# mosfets.net
KiCad netlist of a schematic drawn in Altium Designer
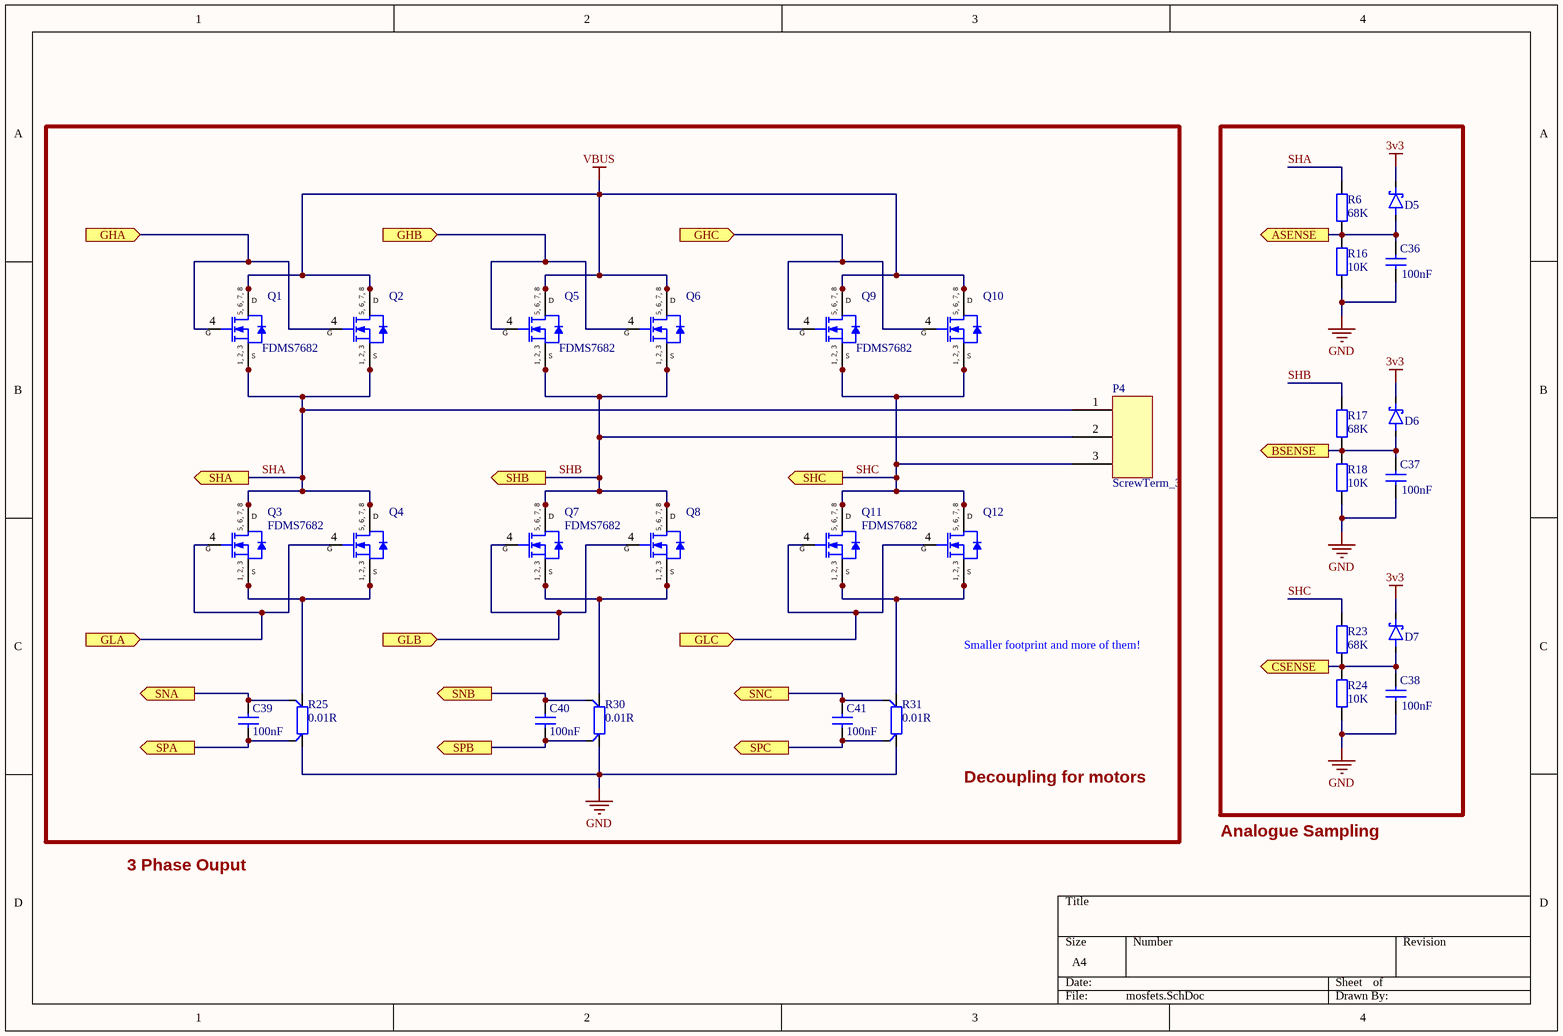
[diagram p0: mosfets.SchDoc]

(export (version "E")
  (design (tool "Eeschema 10.0.6"))
  (components
    (comp (ref "C36")
      (value "100nF")
      (footprint "CAP0402(1005)_N")
      (description "Capacitor")
      (fields (field (name "PART") "cap_generic"))
      (libsource (lib "hitiqlib") (part "cap"))
    )
    (comp (ref "C37")
      (value "100nF")
      (footprint "CAP0402(1005)_N")
      (description "Capacitor")
      (fields (field (name "PART") "cap_generic"))
      (libsource (lib "hitiqlib") (part "cap"))
    )
    (comp (ref "C38")
      (value "100nF")
      (footprint "CAP0402(1005)_N")
      (description "Capacitor")
      (fields (field (name "PART") "cap_generic"))
      (libsource (lib "hitiqlib") (part "cap"))
    )
    (comp (ref "C39")
      (value "100nF")
      (footprint "CAP0402(1005)_N")
      (description "Capacitor")
      (fields (field (name "PART") "cap_generic"))
      (libsource (lib "hitiqlib") (part "cap"))
    )
    (comp (ref "C40")
      (value "100nF")
      (footprint "CAP0402(1005)_N")
      (description "Capacitor")
      (fields (field (name "PART") "cap_generic"))
      (libsource (lib "hitiqlib") (part "cap"))
    )
    (comp (ref "C41")
      (value "100nF")
      (footprint "CAP0402(1005)_N")
      (description "Capacitor")
      (fields (field (name "PART") "cap_generic"))
      (libsource (lib "hitiqlib") (part "cap"))
    )
    (comp (ref "D5")
      (value "Diode_schottky")
      (footprint "SOD523")
      (libsource (lib "myPassives") (part "Diode_schottky"))
    )
    (comp (ref "D6")
      (value "Diode_schottky")
      (footprint "SOD523")
      (libsource (lib "myPassives") (part "Diode_schottky"))
    )
    (comp (ref "D7")
      (value "Diode_schottky")
      (footprint "SOD523")
      (libsource (lib "myPassives") (part "Diode_schottky"))
    )
    (comp (ref "P4")
      (value "ScrewTerm_3")
      (footprint "ScrewTerm_3")
      (libsource (lib "Seeed") (part "ScrewTerm_3"))
    )
    (comp (ref "Q1") (value "FDMS7682") (footprint "PQFN8_5x6") (libsource (lib "myLibs") (part "FDMS7682")))
    (comp (ref "Q2") (value "FDMS7682") (footprint "PQFN8_5x6") (libsource (lib "myLibs") (part "FDMS7682")))
    (comp (ref "Q3") (value "FDMS7682") (footprint "PQFN8_5x6") (libsource (lib "myLibs") (part "FDMS7682")))
    (comp (ref "Q4") (value "FDMS7682") (footprint "PQFN8_5x6") (libsource (lib "myLibs") (part "FDMS7682")))
    (comp (ref "Q5") (value "FDMS7682") (footprint "PQFN8_5x6") (libsource (lib "myLibs") (part "FDMS7682")))
    (comp (ref "Q6") (value "FDMS7682") (footprint "PQFN8_5x6") (libsource (lib "myLibs") (part "FDMS7682")))
    (comp (ref "Q7") (value "FDMS7682") (footprint "PQFN8_5x6") (libsource (lib "myLibs") (part "FDMS7682")))
    (comp (ref "Q8") (value "FDMS7682") (footprint "PQFN8_5x6") (libsource (lib "myLibs") (part "FDMS7682")))
    (comp (ref "Q9") (value "FDMS7682") (footprint "PQFN8_5x6") (libsource (lib "myLibs") (part "FDMS7682")))
    (comp (ref "Q10") (value "FDMS7682") (footprint "PQFN8_5x6") (libsource (lib "myLibs") (part "FDMS7682")))
    (comp (ref "Q11") (value "FDMS7682") (footprint "PQFN8_5x6") (libsource (lib "myLibs") (part "FDMS7682")))
    (comp (ref "Q12") (value "FDMS7682") (footprint "PQFN8_5x6") (libsource (lib "myLibs") (part "FDMS7682")))
    (comp (ref "R6")
      (value "68K")
      (footprint "RESC0402(1005)_N")
      (description "Resistor")
      (fields (field (name "PART") "res_generic"))
      (libsource (lib "hitiqlib") (part "Resistor"))
    )
    (comp (ref "R16")
      (value "10K")
      (footprint "RESC0402(1005)_N")
      (description "Resistor")
      (fields (field (name "PART") "res_generic"))
      (libsource (lib "hitiqlib") (part "Resistor"))
    )
    (comp (ref "R17")
      (value "68K")
      (footprint "RESC0402(1005)_N")
      (description "Resistor")
      (fields (field (name "PART") "res_generic"))
      (libsource (lib "hitiqlib") (part "Resistor"))
    )
    (comp (ref "R18")
      (value "10K")
      (footprint "RESC0402(1005)_N")
      (description "Resistor")
      (fields (field (name "PART") "res_generic"))
      (libsource (lib "hitiqlib") (part "Resistor"))
    )
    (comp (ref "R23")
      (value "68K")
      (footprint "RESC0402(1005)_N")
      (description "Resistor")
      (fields (field (name "PART") "res_generic"))
      (libsource (lib "hitiqlib") (part "Resistor"))
    )
    (comp (ref "R24")
      (value "10K")
      (footprint "RESC0402(1005)_N")
      (description "Resistor")
      (fields (field (name "PART") "res_generic"))
      (libsource (lib "hitiqlib") (part "Resistor"))
    )
    (comp (ref "R25")
      (value "0.01R")
      (footprint "RESC1206_kelvin")
      (description "Kelvin connection resistor")
      (fields (field (name "PART") "Generic_res_kelvin"))
      (libsource (lib "hitiqlib") (part "Resistor_kelvin"))
    )
    (comp (ref "R30")
      (value "0.01R")
      (footprint "RESC1206_kelvin")
      (description "Kelvin connection resistor")
      (fields (field (name "PART") "Generic_res_kelvin"))
      (libsource (lib "hitiqlib") (part "Resistor_kelvin"))
    )
    (comp (ref "R31")
      (value "0.01R")
      (footprint "RESC1206_kelvin")
      (description "Kelvin connection resistor")
      (fields (field (name "PART") "Generic_res_kelvin"))
      (libsource (lib "hitiqlib") (part "Resistor_kelvin"))
    )
  )
  (nets
    (net (code "1") (name "/ASENSE") (class "Default")
      (node (ref "C36") (pin "2") (pintype "passive"))
      (node (ref "D5") (pin "2") (pintype "passive"))
      (node (ref "R16") (pin "2") (pintype "passive"))
      (node (ref "R6") (pin "1") (pintype "passive"))
    )
    (net (code "2") (name "/BSENSE") (class "Default")
      (node (ref "C37") (pin "2") (pintype "passive"))
      (node (ref "D6") (pin "2") (pintype "passive"))
      (node (ref "R17") (pin "1") (pintype "passive"))
      (node (ref "R18") (pin "2") (pintype "passive"))
    )
    (net (code "3") (name "/CSENSE") (class "Default")
      (node (ref "C38") (pin "2") (pintype "passive"))
      (node (ref "D7") (pin "2") (pintype "passive"))
      (node (ref "R23") (pin "1") (pintype "passive"))
      (node (ref "R24") (pin "2") (pintype "passive"))
    )
    (net (code "4") (name "/GHA") (class "Default")
      (node (ref "Q1") (pin "4") (pinfunction "G_4") (pintype "passive"))
      (node (ref "Q2") (pin "4") (pinfunction "G_4") (pintype "passive"))
    )
    (net (code "5") (name "/GHB") (class "Default")
      (node (ref "Q5") (pin "4") (pinfunction "G_4") (pintype "passive"))
      (node (ref "Q6") (pin "4") (pinfunction "G_4") (pintype "passive"))
    )
    (net (code "6") (name "/GHC") (class "Default")
      (node (ref "Q10") (pin "4") (pinfunction "G_4") (pintype "passive"))
      (node (ref "Q9") (pin "4") (pinfunction "G_4") (pintype "passive"))
    )
    (net (code "7") (name "/GLA") (class "Default")
      (node (ref "Q3") (pin "4") (pinfunction "G_4") (pintype "passive"))
      (node (ref "Q4") (pin "4") (pinfunction "G_4") (pintype "passive"))
    )
    (net (code "8") (name "/GLB") (class "Default")
      (node (ref "Q7") (pin "4") (pinfunction "G_4") (pintype "passive"))
      (node (ref "Q8") (pin "4") (pinfunction "G_4") (pintype "passive"))
    )
    (net (code "9") (name "/GLC") (class "Default")
      (node (ref "Q11") (pin "4") (pinfunction "G_4") (pintype "passive"))
      (node (ref "Q12") (pin "4") (pinfunction "G_4") (pintype "passive"))
    )
    (net (code "10") (name "/SHA") (class "Default")
      (node (ref "P4") (pin "1") (pintype "passive"))
      (node (ref "Q1") (pin "1") (pinfunction "S_1") (pintype "passive"))
      (node (ref "Q1") (pin "2") (pinfunction "S_2") (pintype "power_in"))
      (node (ref "Q1") (pin "3") (pinfunction "S_3") (pintype "power_in"))
      (node (ref "Q2") (pin "1") (pinfunction "S_1") (pintype "passive"))
      (node (ref "Q2") (pin "2") (pinfunction "S_2") (pintype "power_in"))
      (node (ref "Q2") (pin "3") (pinfunction "S_3") (pintype "power_in"))
      (node (ref "Q3") (pin "0") (pinfunction "D_0") (pintype "passive"))
      (node (ref "Q3") (pin "5") (pinfunction "D_5") (pintype "passive"))
      (node (ref "Q3") (pin "6") (pinfunction "D_6") (pintype "passive"))
      (node (ref "Q3") (pin "7") (pinfunction "D_7") (pintype "passive"))
      (node (ref "Q3") (pin "8") (pinfunction "D_8") (pintype "passive"))
      (node (ref "Q4") (pin "0") (pinfunction "D_0") (pintype "passive"))
      (node (ref "Q4") (pin "5") (pinfunction "D_5") (pintype "passive"))
      (node (ref "Q4") (pin "6") (pinfunction "D_6") (pintype "passive"))
      (node (ref "Q4") (pin "7") (pinfunction "D_7") (pintype "passive"))
      (node (ref "Q4") (pin "8") (pinfunction "D_8") (pintype "passive"))
      (node (ref "R6") (pin "2") (pintype "passive"))
    )
    (net (code "11") (name "/SHB") (class "Default")
      (node (ref "P4") (pin "2") (pintype "passive"))
      (node (ref "Q5") (pin "1") (pinfunction "S_1") (pintype "passive"))
      (node (ref "Q5") (pin "2") (pinfunction "S_2") (pintype "power_in"))
      (node (ref "Q5") (pin "3") (pinfunction "S_3") (pintype "power_in"))
      (node (ref "Q6") (pin "1") (pinfunction "S_1") (pintype "passive"))
      (node (ref "Q6") (pin "2") (pinfunction "S_2") (pintype "power_in"))
      (node (ref "Q6") (pin "3") (pinfunction "S_3") (pintype "power_in"))
      (node (ref "Q7") (pin "0") (pinfunction "D_0") (pintype "passive"))
      (node (ref "Q7") (pin "5") (pinfunction "D_5") (pintype "passive"))
      (node (ref "Q7") (pin "6") (pinfunction "D_6") (pintype "passive"))
      (node (ref "Q7") (pin "7") (pinfunction "D_7") (pintype "passive"))
      (node (ref "Q7") (pin "8") (pinfunction "D_8") (pintype "passive"))
      (node (ref "Q8") (pin "0") (pinfunction "D_0") (pintype "passive"))
      (node (ref "Q8") (pin "5") (pinfunction "D_5") (pintype "passive"))
      (node (ref "Q8") (pin "6") (pinfunction "D_6") (pintype "passive"))
      (node (ref "Q8") (pin "7") (pinfunction "D_7") (pintype "passive"))
      (node (ref "Q8") (pin "8") (pinfunction "D_8") (pintype "passive"))
      (node (ref "R17") (pin "2") (pintype "passive"))
    )
    (net (code "12") (name "/SHC") (class "Default")
      (node (ref "P4") (pin "3") (pintype "passive"))
      (node (ref "Q10") (pin "1") (pinfunction "S_1") (pintype "passive"))
      (node (ref "Q10") (pin "2") (pinfunction "S_2") (pintype "power_in"))
      (node (ref "Q10") (pin "3") (pinfunction "S_3") (pintype "power_in"))
      (node (ref "Q11") (pin "0") (pinfunction "D_0") (pintype "passive"))
      (node (ref "Q11") (pin "5") (pinfunction "D_5") (pintype "passive"))
      (node (ref "Q11") (pin "6") (pinfunction "D_6") (pintype "passive"))
      (node (ref "Q11") (pin "7") (pinfunction "D_7") (pintype "passive"))
      (node (ref "Q11") (pin "8") (pinfunction "D_8") (pintype "passive"))
      (node (ref "Q12") (pin "0") (pinfunction "D_0") (pintype "passive"))
      (node (ref "Q12") (pin "5") (pinfunction "D_5") (pintype "passive"))
      (node (ref "Q12") (pin "6") (pinfunction "D_6") (pintype "passive"))
      (node (ref "Q12") (pin "7") (pinfunction "D_7") (pintype "passive"))
      (node (ref "Q12") (pin "8") (pinfunction "D_8") (pintype "passive"))
      (node (ref "Q9") (pin "1") (pinfunction "S_1") (pintype "passive"))
      (node (ref "Q9") (pin "2") (pinfunction "S_2") (pintype "power_in"))
      (node (ref "Q9") (pin "3") (pinfunction "S_3") (pintype "power_in"))
      (node (ref "R23") (pin "2") (pintype "passive"))
    )
    (net (code "13") (name "/SNA") (class "Default")
      (node (ref "C39") (pin "2") (pintype "passive"))
      (node (ref "R25") (pin "3") (pinfunction "3_3") (pintype "passive"))
    )
    (net (code "14") (name "/SNB") (class "Default")
      (node (ref "C40") (pin "2") (pintype "passive"))
      (node (ref "R30") (pin "3") (pinfunction "3_3") (pintype "passive"))
    )
    (net (code "15") (name "/SNC") (class "Default")
      (node (ref "C41") (pin "2") (pintype "passive"))
      (node (ref "R31") (pin "3") (pinfunction "3_3") (pintype "passive"))
    )
    (net (code "16") (name "/SPA") (class "Default")
      (node (ref "C39") (pin "1") (pintype "passive"))
      (node (ref "R25") (pin "4") (pinfunction "4_4") (pintype "passive"))
    )
    (net (code "17") (name "/SPB") (class "Default")
      (node (ref "C40") (pin "1") (pintype "passive"))
      (node (ref "R30") (pin "4") (pinfunction "4_4") (pintype "passive"))
    )
    (net (code "18") (name "/SPC") (class "Default")
      (node (ref "C41") (pin "1") (pintype "passive"))
      (node (ref "R31") (pin "4") (pinfunction "4_4") (pintype "passive"))
    )
    (net (code "19") (name "3v3") (class "Default")
      (node (ref "D5") (pin "1") (pintype "passive"))
      (node (ref "D6") (pin "1") (pintype "passive"))
      (node (ref "D7") (pin "1") (pintype "passive"))
    )
    (net (code "20") (name "GND") (class "Default")
      (node (ref "C36") (pin "1") (pintype "passive"))
      (node (ref "C37") (pin "1") (pintype "passive"))
      (node (ref "C38") (pin "1") (pintype "passive"))
      (node (ref "R16") (pin "1") (pintype "passive"))
      (node (ref "R18") (pin "1") (pintype "passive"))
      (node (ref "R24") (pin "1") (pintype "passive"))
      (node (ref "R25") (pin "2") (pintype "passive"))
      (node (ref "R30") (pin "2") (pintype "passive"))
      (node (ref "R31") (pin "2") (pintype "passive"))
    )
    (net (code "21") (name "Net-(Q3-S-Pad1)") (class "Default")
      (node (ref "Q3") (pin "1") (pinfunction "S_1") (pintype "passive"))
      (node (ref "Q3") (pin "2") (pinfunction "S_2") (pintype "power_in"))
      (node (ref "Q3") (pin "3") (pinfunction "S_3") (pintype "power_in"))
      (node (ref "Q4") (pin "1") (pinfunction "S_1") (pintype "passive"))
      (node (ref "Q4") (pin "2") (pinfunction "S_2") (pintype "power_in"))
      (node (ref "Q4") (pin "3") (pinfunction "S_3") (pintype "power_in"))
      (node (ref "R25") (pin "1") (pintype "passive"))
    )
    (net (code "22") (name "Net-(Q7-S-Pad1)") (class "Default")
      (node (ref "Q7") (pin "1") (pinfunction "S_1") (pintype "passive"))
      (node (ref "Q7") (pin "2") (pinfunction "S_2") (pintype "power_in"))
      (node (ref "Q7") (pin "3") (pinfunction "S_3") (pintype "power_in"))
      (node (ref "Q8") (pin "1") (pinfunction "S_1") (pintype "passive"))
      (node (ref "Q8") (pin "2") (pinfunction "S_2") (pintype "power_in"))
      (node (ref "Q8") (pin "3") (pinfunction "S_3") (pintype "power_in"))
      (node (ref "R30") (pin "1") (pintype "passive"))
    )
    (net (code "23") (name "Net-(Q11-S-Pad1)") (class "Default")
      (node (ref "Q11") (pin "1") (pinfunction "S_1") (pintype "passive"))
      (node (ref "Q11") (pin "2") (pinfunction "S_2") (pintype "power_in"))
      (node (ref "Q11") (pin "3") (pinfunction "S_3") (pintype "power_in"))
      (node (ref "Q12") (pin "1") (pinfunction "S_1") (pintype "passive"))
      (node (ref "Q12") (pin "2") (pinfunction "S_2") (pintype "power_in"))
      (node (ref "Q12") (pin "3") (pinfunction "S_3") (pintype "power_in"))
      (node (ref "R31") (pin "1") (pintype "passive"))
    )
    (net (code "24") (name "VBUS") (class "Default")
      (node (ref "Q1") (pin "0") (pinfunction "D_0") (pintype "passive"))
      (node (ref "Q1") (pin "5") (pinfunction "D_5") (pintype "passive"))
      (node (ref "Q1") (pin "6") (pinfunction "D_6") (pintype "passive"))
      (node (ref "Q1") (pin "7") (pinfunction "D_7") (pintype "passive"))
      (node (ref "Q1") (pin "8") (pinfunction "D_8") (pintype "passive"))
      (node (ref "Q10") (pin "0") (pinfunction "D_0") (pintype "passive"))
      (node (ref "Q10") (pin "5") (pinfunction "D_5") (pintype "passive"))
      (node (ref "Q10") (pin "6") (pinfunction "D_6") (pintype "passive"))
      (node (ref "Q10") (pin "7") (pinfunction "D_7") (pintype "passive"))
      (node (ref "Q10") (pin "8") (pinfunction "D_8") (pintype "passive"))
      (node (ref "Q2") (pin "0") (pinfunction "D_0") (pintype "passive"))
      (node (ref "Q2") (pin "5") (pinfunction "D_5") (pintype "passive"))
      (node (ref "Q2") (pin "6") (pinfunction "D_6") (pintype "passive"))
      (node (ref "Q2") (pin "7") (pinfunction "D_7") (pintype "passive"))
      (node (ref "Q2") (pin "8") (pinfunction "D_8") (pintype "passive"))
      (node (ref "Q5") (pin "0") (pinfunction "D_0") (pintype "passive"))
      (node (ref "Q5") (pin "5") (pinfunction "D_5") (pintype "passive"))
      (node (ref "Q5") (pin "6") (pinfunction "D_6") (pintype "passive"))
      (node (ref "Q5") (pin "7") (pinfunction "D_7") (pintype "passive"))
      (node (ref "Q5") (pin "8") (pinfunction "D_8") (pintype "passive"))
      (node (ref "Q6") (pin "0") (pinfunction "D_0") (pintype "passive"))
      (node (ref "Q6") (pin "5") (pinfunction "D_5") (pintype "passive"))
      (node (ref "Q6") (pin "6") (pinfunction "D_6") (pintype "passive"))
      (node (ref "Q6") (pin "7") (pinfunction "D_7") (pintype "passive"))
      (node (ref "Q6") (pin "8") (pinfunction "D_8") (pintype "passive"))
      (node (ref "Q9") (pin "0") (pinfunction "D_0") (pintype "passive"))
      (node (ref "Q9") (pin "5") (pinfunction "D_5") (pintype "passive"))
      (node (ref "Q9") (pin "6") (pinfunction "D_6") (pintype "passive"))
      (node (ref "Q9") (pin "7") (pinfunction "D_7") (pintype "passive"))
      (node (ref "Q9") (pin "8") (pinfunction "D_8") (pintype "passive"))
    )
  )
)
